# cr2032_powered_devel_board.net
KiCad netlist of a schematic drawn in EAGLE
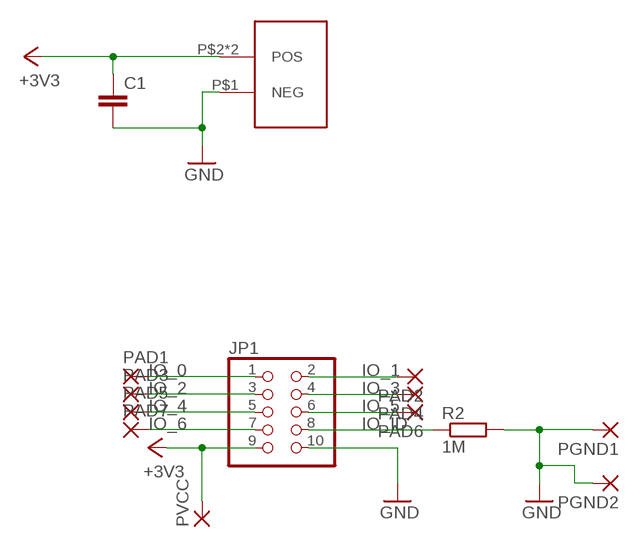
[diagram p0: schematic, sheet 1]

(export (version "E")
  (design (tool "Eeschema 10.0.6"))
  (components
    (comp (ref "C1")
      (value "C-EU025-030X050")
      (footprint "eagle-import:C025-030X050")
      (libsource (lib "eagle-import") (part "C-EU025-030X050"))
    )
    (comp (ref "JP1")
      (value "PINHD-2X5")
      (footprint "eagle-import:2X05")
      (libsource (lib "eagle-import") (part "PINHD-2X5"))
    )
    (comp (ref "PAD1")
      (value "1,6/0,8")
      (footprint "eagle-import:1,6_0,8")
      (libsource (lib "eagle-import") (part "1,6/0,8"))
    )
    (comp (ref "PAD2")
      (value "1,6/0,8")
      (footprint "eagle-import:1,6_0,8")
      (libsource (lib "eagle-import") (part "1,6/0,8"))
    )
    (comp (ref "PAD3")
      (value "1,6/0,8")
      (footprint "eagle-import:1,6_0,8")
      (libsource (lib "eagle-import") (part "1,6/0,8"))
    )
    (comp (ref "PAD4")
      (value "1,6/0,8")
      (footprint "eagle-import:1,6_0,8")
      (libsource (lib "eagle-import") (part "1,6/0,8"))
    )
    (comp (ref "PAD5")
      (value "1,6/0,8")
      (footprint "eagle-import:1,6_0,8")
      (libsource (lib "eagle-import") (part "1,6/0,8"))
    )
    (comp (ref "PAD6")
      (value "1,6/0,8")
      (footprint "eagle-import:1,6_0,8")
      (libsource (lib "eagle-import") (part "1,6/0,8"))
    )
    (comp (ref "PAD7")
      (value "1,6/0,8")
      (footprint "eagle-import:1,6_0,8")
      (libsource (lib "eagle-import") (part "1,6/0,8"))
    )
    (comp (ref "PGND1")
      (value "1,6/0,8")
      (footprint "eagle-import:1,6_0,8")
      (libsource (lib "eagle-import") (part "1,6/0,8"))
    )
    (comp (ref "PGND2")
      (value "1,6/0,8")
      (footprint "eagle-import:1,6_0,8")
      (libsource (lib "eagle-import") (part "1,6/0,8"))
    )
    (comp (ref "PVCC")
      (value "1,6/0,8")
      (footprint "eagle-import:1,6_0,8")
      (libsource (lib "eagle-import") (part "1,6/0,8"))
    )
    (comp (ref "R2")
      (value "1M")
      (footprint "eagle-import:R0402")
      (libsource (lib "eagle-import") (part "R-EU_R0402"))
    )
    (comp (ref "U$1")
      (value "CR2032_CLIP")
      (footprint "eagle-import:CR2032_CLIP")
      (libsource (lib "eagle-import") (part "CR2032_CLIP"))
    )
  )
  (nets
    (net (code "1") (name "+3V3") (class "Default")
      (node (ref "C1") (pin "1") (pinfunction "1_1") (pintype "passive"))
      (node (ref "JP1") (pin "9") (pinfunction "9_9") (pintype "passive"))
      (node (ref "PVCC") (pin "1") (pinfunction "P_1") (pintype "passive"))
      (node (ref "U$1") (pin "P$2") (pinfunction "POS_P$2") (pintype "bidirectional"))
      (node (ref "U$1") (pin "P$3") (pinfunction "POS_P$3") (pintype "bidirectional"))
    )
    (net (code "2") (name "/IO_0") (class "Default")
      (node (ref "JP1") (pin "1") (pinfunction "1_1") (pintype "passive"))
      (node (ref "PAD1") (pin "1") (pinfunction "P_1") (pintype "passive"))
    )
    (net (code "3") (name "/IO_1") (class "Default")
      (node (ref "JP1") (pin "2") (pinfunction "2_2") (pintype "passive"))
      (node (ref "PAD2") (pin "1") (pinfunction "P_1") (pintype "passive"))
    )
    (net (code "4") (name "/IO_2") (class "Default")
      (node (ref "JP1") (pin "3") (pinfunction "3_3") (pintype "passive"))
      (node (ref "PAD3") (pin "1") (pinfunction "P_1") (pintype "passive"))
    )
    (net (code "5") (name "/IO_3") (class "Default")
      (node (ref "JP1") (pin "4") (pinfunction "4_4") (pintype "passive"))
      (node (ref "PAD4") (pin "1") (pinfunction "P_1") (pintype "passive"))
    )
    (net (code "6") (name "/IO_4") (class "Default")
      (node (ref "JP1") (pin "5") (pinfunction "5_5") (pintype "passive"))
      (node (ref "PAD5") (pin "1") (pinfunction "P_1") (pintype "passive"))
    )
    (net (code "7") (name "/IO_5") (class "Default")
      (node (ref "JP1") (pin "6") (pinfunction "6_6") (pintype "passive"))
      (node (ref "PAD6") (pin "1") (pinfunction "P_1") (pintype "passive"))
    )
    (net (code "8") (name "/IO_6") (class "Default")
      (node (ref "JP1") (pin "7") (pinfunction "7_7") (pintype "passive"))
      (node (ref "PAD7") (pin "1") (pinfunction "P_1") (pintype "passive"))
    )
    (net (code "9") (name "/IO_ID") (class "Default")
      (node (ref "JP1") (pin "8") (pinfunction "8_8") (pintype "passive"))
      (node (ref "R2") (pin "1") (pinfunction "1_1") (pintype "passive"))
    )
    (net (code "10") (name "GND") (class "Default")
      (node (ref "C1") (pin "2") (pinfunction "2_2") (pintype "passive"))
      (node (ref "JP1") (pin "10") (pinfunction "10_10") (pintype "passive"))
      (node (ref "PGND1") (pin "1") (pinfunction "P_1") (pintype "passive"))
      (node (ref "PGND2") (pin "1") (pinfunction "P_1") (pintype "passive"))
      (node (ref "R2") (pin "2") (pinfunction "2_2") (pintype "passive"))
      (node (ref "U$1") (pin "P$1") (pinfunction "NEG_P$1") (pintype "bidirectional"))
    )
  )
)
